# phMeter_v1_0.net
KiCad netlist of a schematic drawn in EAGLE
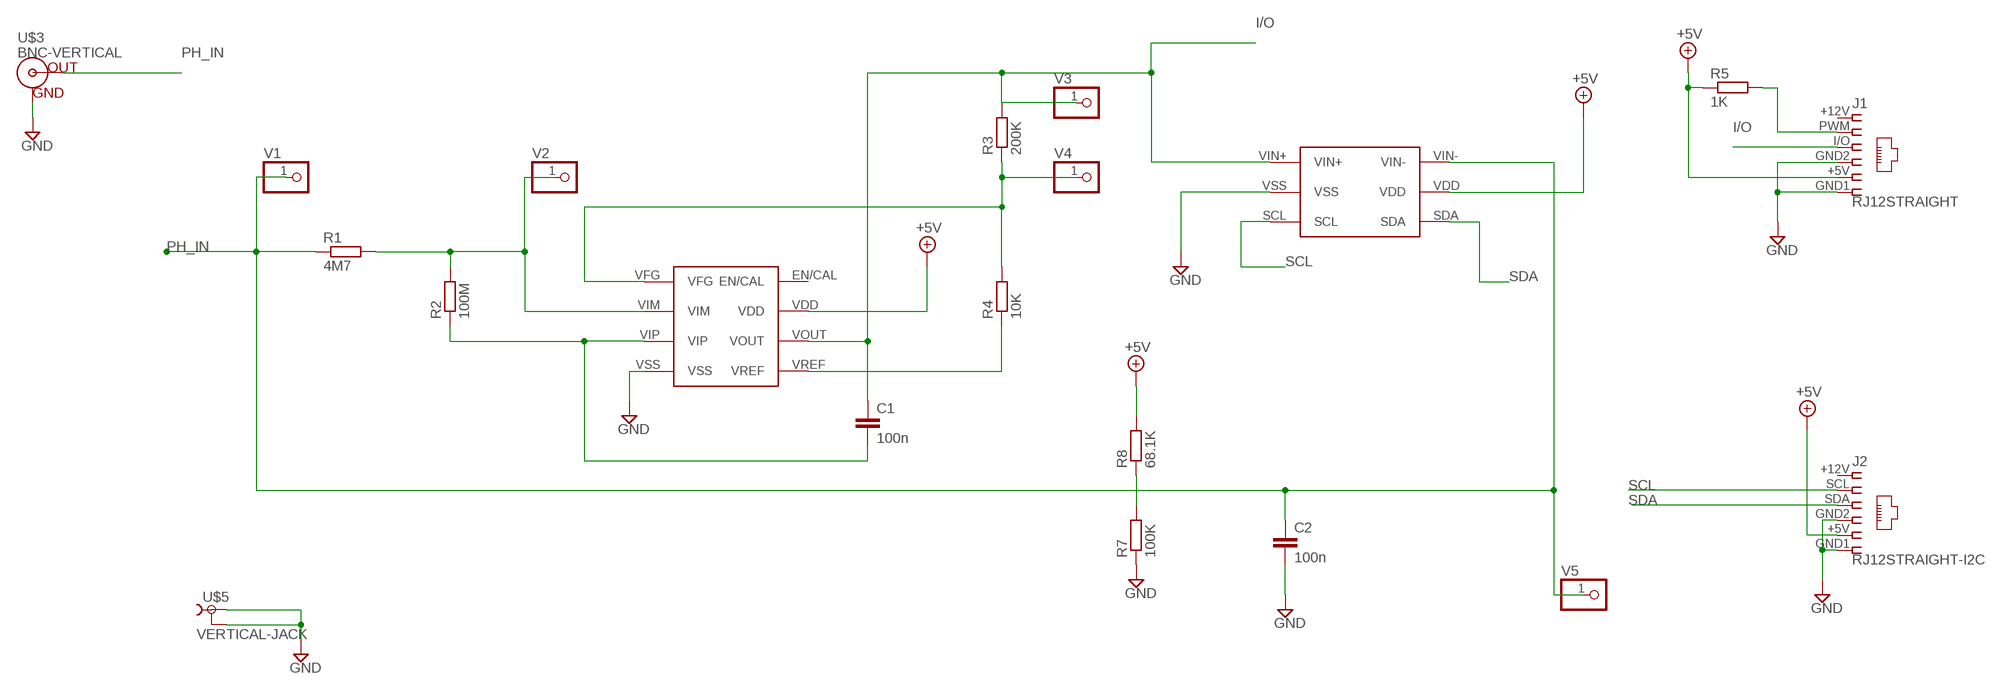
[diagram p0: schematic, sheet 1]

(export (version "E")
  (design (tool "Eeschema 10.0.6"))
  (components
    (comp (ref "C1")
      (value "100n")
      (footprint "eagle-import:C1206")
      (libsource (lib "eagle-import") (part "C-EUC1206"))
    )
    (comp (ref "C2")
      (value "100n")
      (footprint "eagle-import:C1206")
      (libsource (lib "eagle-import") (part "C-EUC1206"))
    )
    (comp (ref "J1")
      (value "RJ12STRAIGHT")
      (footprint "eagle-import:RJ12-STRAIGHT")
      (libsource (lib "eagle-import") (part "RJ12STRAIGHT"))
    )
    (comp (ref "J2")
      (value "RJ12STRAIGHT-I2C")
      (footprint "eagle-import:RJ12-STRAIGHT-I2C")
      (libsource (lib "eagle-import") (part "RJ12STRAIGHT-I2C"))
    )
    (comp (ref "R1")
      (value "4M7")
      (footprint "eagle-import:R1206")
      (libsource (lib "eagle-import") (part "R-EU_R1206"))
    )
    (comp (ref "R2")
      (value "100M")
      (footprint "eagle-import:R1206")
      (libsource (lib "eagle-import") (part "R-EU_R1206"))
    )
    (comp (ref "R3")
      (value "200K")
      (footprint "eagle-import:R1206")
      (libsource (lib "eagle-import") (part "R-EU_R1206"))
    )
    (comp (ref "R4")
      (value "10K")
      (footprint "eagle-import:R1206")
      (libsource (lib "eagle-import") (part "R-EU_R1206"))
    )
    (comp (ref "R5")
      (value "1K")
      (footprint "eagle-import:R1206")
      (libsource (lib "eagle-import") (part "R-EU_R1206"))
    )
    (comp (ref "R7")
      (value "100K")
      (footprint "eagle-import:R1206")
      (libsource (lib "eagle-import") (part "R-EU_R1206"))
    )
    (comp (ref "R8")
      (value "68.1K")
      (footprint "eagle-import:R1206")
      (libsource (lib "eagle-import") (part "R-EU_R1206"))
    )
    (comp (ref "U$1")
      (value "MCP3425")
      (footprint "eagle-import:SOT-23-6")
      (libsource (lib "eagle-import") (part "MCP3425"))
    )
    (comp (ref "U$2")
      (value "MCP6N11010E")
      (footprint "eagle-import:SOIC")
      (libsource (lib "eagle-import") (part "MCP6N11010E"))
    )
    (comp (ref "U$3")
      (value "BNC-VERTICAL")
      (footprint "eagle-import:BNC-VERTICAL")
      (libsource (lib "eagle-import") (part "BNC-VERTICAL"))
    )
    (comp (ref "U$5")
      (value "VERTICAL-JACK")
      (footprint "eagle-import:VERTICAL-JACK")
      (libsource (lib "eagle-import") (part "VERTICAL-JACK"))
    )
    (comp (ref "V1")
      (value "PINHD-1X1")
      (footprint "eagle-import:1X01")
      (libsource (lib "eagle-import") (part "PINHD-1X1"))
    )
    (comp (ref "V2")
      (value "PINHD-1X1")
      (footprint "eagle-import:1X01")
      (libsource (lib "eagle-import") (part "PINHD-1X1"))
    )
    (comp (ref "V3")
      (value "PINHD-1X1")
      (footprint "eagle-import:1X01")
      (libsource (lib "eagle-import") (part "PINHD-1X1"))
    )
    (comp (ref "V4")
      (value "PINHD-1X1")
      (footprint "eagle-import:1X01")
      (libsource (lib "eagle-import") (part "PINHD-1X1"))
    )
    (comp (ref "V5")
      (value "PINHD-1X1")
      (footprint "eagle-import:1X01")
      (libsource (lib "eagle-import") (part "PINHD-1X1"))
    )
  )
  (nets
    (net (code "1") (name "+5V") (class "Default")
      (node (ref "J1") (pin "+5V") (pinfunction "5_+5V") (pintype "bidirectional"))
      (node (ref "J2") (pin "+5V") (pinfunction "5_+5V") (pintype "bidirectional"))
      (node (ref "R5") (pin "1") (pinfunction "1_1") (pintype "passive"))
      (node (ref "R8") (pin "2") (pinfunction "2_2") (pintype "passive"))
      (node (ref "U$1") (pin "VDD") (pinfunction "VDD_VDD") (pintype "bidirectional"))
      (node (ref "U$2") (pin "VDD") (pinfunction "VDD_VDD") (pintype "bidirectional"))
    )
    (net (code "2") (name "/I{slash}O") (class "Default")
      (node (ref "C1") (pin "1") (pinfunction "1_1") (pintype "passive"))
      (node (ref "J1") (pin "I/O") (pinfunction "3_I/O") (pintype "bidirectional"))
      (node (ref "R3") (pin "2") (pinfunction "2_2") (pintype "passive"))
      (node (ref "U$1") (pin "VIN+") (pinfunction "VIN+_VIN+") (pintype "bidirectional"))
      (node (ref "U$2") (pin "VOUT") (pinfunction "VOUT_VOUT") (pintype "bidirectional"))
      (node (ref "V3") (pin "1") (pinfunction "1_1") (pintype "passive"))
    )
    (net (code "3") (name "/PH_IN") (class "Default")
      (node (ref "C2") (pin "1") (pinfunction "1_1") (pintype "passive"))
      (node (ref "R1") (pin "1") (pinfunction "1_1") (pintype "passive"))
      (node (ref "U$1") (pin "VIN-") (pinfunction "VIN-_VIN-") (pintype "bidirectional"))
      (node (ref "U$3") (pin "S") (pinfunction "OUT_S") (pintype "bidirectional"))
      (node (ref "V1") (pin "1") (pinfunction "1_1") (pintype "passive"))
      (node (ref "V5") (pin "1") (pinfunction "1_1") (pintype "passive"))
    )
    (net (code "4") (name "/SCL") (class "Default")
      (node (ref "J2") (pin "SCL") (pinfunction "2_SCL") (pintype "bidirectional"))
      (node (ref "U$1") (pin "SCL") (pinfunction "SCL_SCL") (pintype "bidirectional"))
    )
    (net (code "5") (name "/SDA") (class "Default")
      (node (ref "J2") (pin "SDA") (pinfunction "3_SDA") (pintype "bidirectional"))
      (node (ref "U$1") (pin "SDA") (pinfunction "SDA_SDA") (pintype "bidirectional"))
    )
    (net (code "6") (name "GND") (class "Default")
      (node (ref "C2") (pin "2") (pinfunction "2_2") (pintype "passive"))
      (node (ref "J1") (pin "GND1") (pinfunction "6_GND1") (pintype "bidirectional"))
      (node (ref "J1") (pin "GND2") (pinfunction "4_GND2") (pintype "bidirectional"))
      (node (ref "J2") (pin "GND1") (pinfunction "6_GND1") (pintype "bidirectional"))
      (node (ref "J2") (pin "GND2") (pinfunction "4_GND2") (pintype "bidirectional"))
      (node (ref "R7") (pin "1") (pinfunction "1_1") (pintype "passive"))
      (node (ref "U$1") (pin "VSS") (pinfunction "VSS_VSS") (pintype "bidirectional"))
      (node (ref "U$2") (pin "VSS") (pinfunction "VSS_VSS") (pintype "bidirectional"))
      (node (ref "U$3") (pin "G") (pinfunction "GND_G") (pintype "bidirectional"))
      (node (ref "U$5") (pin "P$1") (pinfunction "1_P$1") (pintype "passive"))
      (node (ref "U$5") (pin "P$2") (pinfunction "2_P$2") (pintype "passive"))
    )
    (net (code "7") (name "Net-(C1-Pad2)") (class "Default")
      (node (ref "C1") (pin "2") (pinfunction "2_2") (pintype "passive"))
      (node (ref "R2") (pin "1") (pinfunction "1_1") (pintype "passive"))
      (node (ref "U$2") (pin "VIP") (pinfunction "VIP_VIP") (pintype "bidirectional"))
    )
    (net (code "8") (name "Net-(J1-2)") (class "Default")
      (node (ref "J1") (pin "PWM") (pinfunction "2_PWM") (pintype "bidirectional"))
      (node (ref "R5") (pin "2") (pinfunction "2_2") (pintype "passive"))
    )
    (net (code "9") (name "Net-(R1-Pad2)") (class "Default")
      (node (ref "R1") (pin "2") (pinfunction "2_2") (pintype "passive"))
      (node (ref "R2") (pin "2") (pinfunction "2_2") (pintype "passive"))
      (node (ref "U$2") (pin "VIM") (pinfunction "VIM_VIM") (pintype "bidirectional"))
      (node (ref "V2") (pin "1") (pinfunction "1_1") (pintype "passive"))
    )
    (net (code "10") (name "Net-(R3-Pad1)") (class "Default")
      (node (ref "R3") (pin "1") (pinfunction "1_1") (pintype "passive"))
      (node (ref "R4") (pin "2") (pinfunction "2_2") (pintype "passive"))
      (node (ref "U$2") (pin "VFG") (pinfunction "VFG_VFG") (pintype "bidirectional"))
      (node (ref "V4") (pin "1") (pinfunction "1_1") (pintype "passive"))
    )
    (net (code "11") (name "Net-(R4-Pad1)") (class "Default")
      (node (ref "R4") (pin "1") (pinfunction "1_1") (pintype "passive"))
      (node (ref "U$2") (pin "VREF") (pinfunction "VREF_VREF") (pintype "bidirectional"))
    )
    (net (code "12") (name "Net-(R7-Pad2)") (class "Default")
      (node (ref "R7") (pin "2") (pinfunction "2_2") (pintype "passive"))
      (node (ref "R8") (pin "1") (pinfunction "1_1") (pintype "passive"))
    )
    (net (code "13") (name "unconnected-(J1-1-Pad+12V)") (class "Default")
      (node (ref "J1") (pin "+12V") (pinfunction "1_+12V") (pintype "bidirectional"))
    )
    (net (code "14") (name "unconnected-(J2-1-Pad+12V)") (class "Default")
      (node (ref "J2") (pin "+12V") (pinfunction "1_+12V") (pintype "bidirectional"))
    )
    (net (code "15") (name "unconnected-(U$2-PadEN{slash}CAL)") (class "Default")
      (node (ref "U$2") (pin "EN/CAL") (pinfunction "EN/CAL_EN/CAL") (pintype "bidirectional"))
    )
  )
)
